# Regulator.net
KiCad netlist of a schematic drawn in Altium Designer
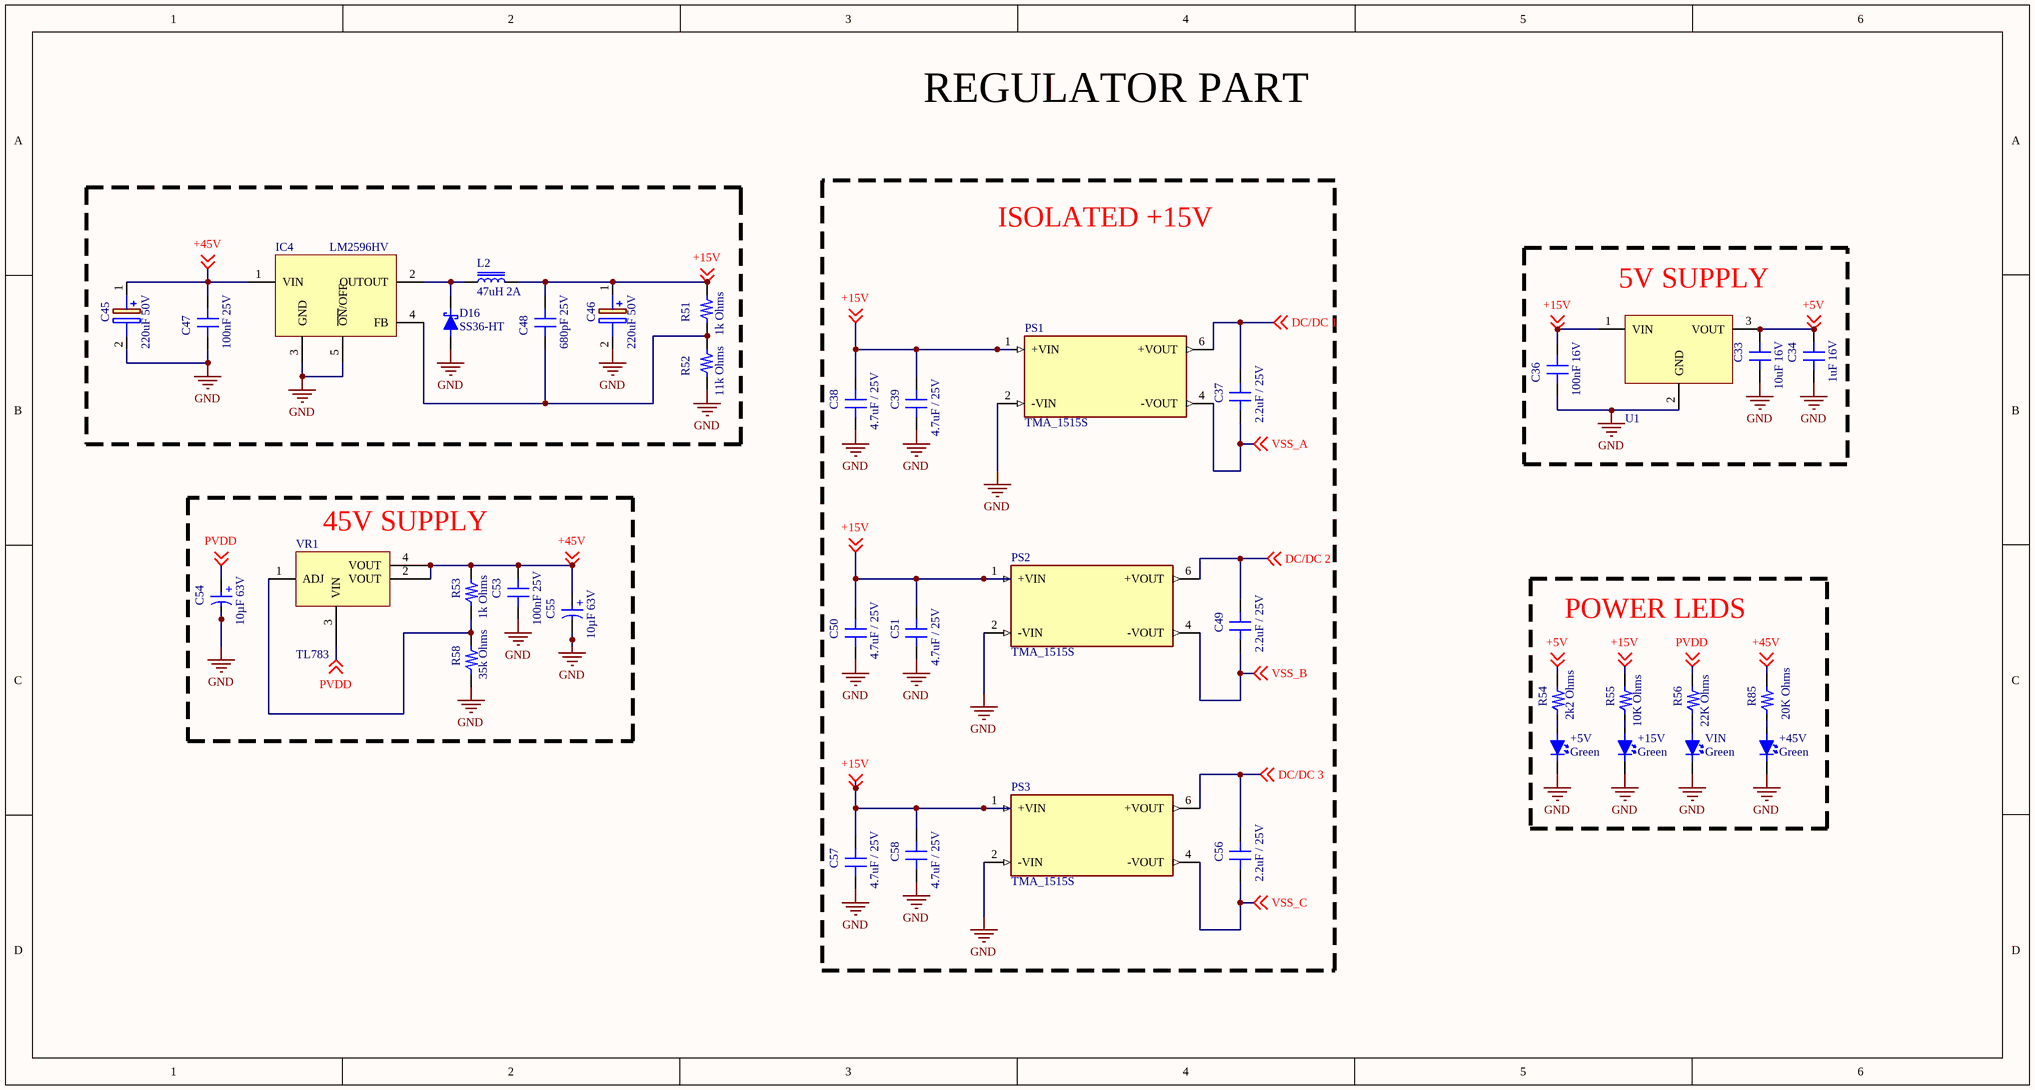
[diagram p0: Regulator.SchDoc]

(export (version "E")
  (design (tool "Eeschema 10.0.6"))
  (components
    (comp (ref "+5V")
      (value "Green")
      (footprint "0805LED")
      (description "0805")
      (libsource (lib "HidroanaSCHLib") (part "LED"))
    )
    (comp (ref "+15V")
      (value "Green")
      (footprint "0805LED")
      (description "0805")
      (libsource (lib "HidroanaSCHLib") (part "LED"))
    )
    (comp (ref "+45V")
      (value "Green")
      (footprint "0805LED")
      (description "0805")
      (libsource (lib "HidroanaSCHLib") (part "LED"))
    )
    (comp (ref "C33")
      (value "10uF 16V")
      (footprint "0805_CAP")
      (libsource (lib "HidroanaSCHLib") (part "CAP_0805"))
    )
    (comp (ref "C34")
      (value "1uF 16V")
      (footprint "0805_CAP")
      (libsource (lib "HidroanaSCHLib") (part "CAP_0805"))
    )
    (comp (ref "C36")
      (value "100nF 16V")
      (footprint "0805_CAP")
      (libsource (lib "HidroanaSCHLib") (part "CAP_0805"))
    )
    (comp (ref "C37")
      (value "2.2uF / 25V")
      (footprint "0805_CAP")
      (libsource (lib "HidroanaSCHLib") (part "CAP_0805"))
    )
    (comp (ref "C38")
      (value "4.7uF / 25V")
      (footprint "0805_CAP")
      (libsource (lib "HidroanaSCHLib") (part "CAP_0805"))
    )
    (comp (ref "C39")
      (value "4.7uF / 25V")
      (footprint "0805_CAP")
      (libsource (lib "HidroanaSCHLib") (part "CAP_0805"))
    )
    (comp (ref "C45")
      (value "220uF 50V")
      (footprint "CAPAE1030X1060N")
      (description "Capacitor Polarised")
      (fields (field (name "MANUFACTURER_PART_NUMBER") "CK1H221M-CRG10"))
      (libsource (lib "HidroanaSCHLib") (part "CK1H221M-CRG10"))
    )
    (comp (ref "C46")
      (value "220uF 50V")
      (footprint "CAPAE1030X1060N")
      (description "Capacitor Polarised")
      (fields (field (name "MANUFACTURER_PART_NUMBER") "CK1H221M-CRG10"))
      (libsource (lib "HidroanaSCHLib") (part "CK1H221M-CRG10"))
    )
    (comp (ref "C47")
      (value "100nF 25V")
      (footprint "0805_CAP")
      (libsource (lib "HidroanaSCHLib") (part "CAP_0805"))
    )
    (comp (ref "C48")
      (value "680pF 25V")
      (footprint "0805_CAP")
      (libsource (lib "HidroanaSCHLib") (part "CAP_0805"))
    )
    (comp (ref "C49")
      (value "2.2uF / 25V")
      (footprint "0805_CAP")
      (libsource (lib "HidroanaSCHLib") (part "CAP_0805"))
    )
    (comp (ref "C50")
      (value "4.7uF / 25V")
      (footprint "0805_CAP")
      (libsource (lib "HidroanaSCHLib") (part "CAP_0805"))
    )
    (comp (ref "C51")
      (value "4.7uF / 25V")
      (footprint "0805_CAP")
      (libsource (lib "HidroanaSCHLib") (part "CAP_0805"))
    )
    (comp (ref "C53")
      (value "100nF 25V")
      (footprint "0805_CAP")
      (libsource (lib "HidroanaSCHLib") (part "CAP_0805"))
    )
    (comp (ref "C54")
      (value "10µF 63V")
      (footprint "WCAP-ATG5_D5H11")
      (description "WCAP-ATG5 Aluminum Electrolytic Capacitor, Radial, THT, D5 x H11mm, 10µF, 63V")
      (fields
        (field (name "MANUFACTURER PART NUMBER") "860020772010")
        (field (name "MANUFACTURER") "Wurth Elektronik")
      )
      (libsource (lib "Hidroana Lib") (part "860020772010"))
    )
    (comp (ref "C55")
      (value "10µF 63V")
      (footprint "WCAP-ATG5_D5H11")
      (description "WCAP-ATG5 Aluminum Electrolytic Capacitor, Radial, THT, D5 x H11mm, 10µF, 63V")
      (fields
        (field (name "MANUFACTURER PART NUMBER") "860020772010")
        (field (name "MANUFACTURER") "Wurth Elektronik")
      )
      (libsource (lib "Hidroana Lib") (part "860020772010"))
    )
    (comp (ref "C56")
      (value "2.2uF / 25V")
      (footprint "0805_CAP")
      (libsource (lib "HidroanaSCHLib") (part "CAP_0805"))
    )
    (comp (ref "C57")
      (value "4.7uF / 25V")
      (footprint "0805_CAP")
      (libsource (lib "HidroanaSCHLib") (part "CAP_0805"))
    )
    (comp (ref "C58")
      (value "4.7uF / 25V")
      (footprint "0805_CAP")
      (libsource (lib "HidroanaSCHLib") (part "CAP_0805"))
    )
    (comp (ref "D16")
      (value "SS36-HT")
      (footprint "DO-214AB")
      (description "Schottky Diode")
      (libsource (lib "HidroanaSCHLib") (part "SS36-214AB-HT"))
    )
    (comp (ref "IC4")
      (value "LM2596HV")
      (footprint "TO-263-5")
      (description "Integrated Circuit")
      (fields
        (field (name "MOUSER PART NUMBER") "926-LM2596S-12")
        (field (name "ARROW PART NUMBER") "LM2596S-12")
      )
      (libsource (lib "HidroanaSCHLib") (part "LM2596HV"))
    )
    (comp (ref "L2")
      (value "47uH 2A")
      (footprint "BOURNS SRR1280")
      (description "FIXED IND 47UH 2.9A 80 MOHM SMD")
      (libsource (lib "HidroanaSCHLib") (part "Inductor"))
    )
    (comp (ref "PS1")
      (value "TMA_1515S")
      (footprint "CONV_TMA_1515S")
      (fields (field (name "MF") "{'manufacturer': u'Traco Power'}"))
      (libsource (lib "TMA_1515S") (part "TMA_1515S"))
    )
    (comp (ref "PS2")
      (value "TMA_1515S")
      (footprint "CONV_TMA_1515S")
      (fields (field (name "MF") "{'manufacturer': u'Traco Power'}"))
      (libsource (lib "TMA_1515S") (part "TMA_1515S"))
    )
    (comp (ref "PS3")
      (value "TMA_1515S")
      (footprint "CONV_TMA_1515S")
      (fields (field (name "MF") "{'manufacturer': u'Traco Power'}"))
      (libsource (lib "TMA_1515S") (part "TMA_1515S"))
    )
    (comp (ref "R51")
      (value "1k Ohms")
      (footprint "0805_RES")
      (description "0805")
      (fields (field (name "POWER") "1/8 W"))
      (libsource (lib "HidroanaSCHLib") (part "RES_0805"))
    )
    (comp (ref "R52")
      (value "11k Ohms")
      (footprint "0805_RES")
      (description "0805")
      (fields (field (name "POWER") "1/8 W"))
      (libsource (lib "HidroanaSCHLib") (part "RES_0805"))
    )
    (comp (ref "R53")
      (value "1k Ohms")
      (footprint "0805_RES")
      (description "0805")
      (fields (field (name "POWER") "1/8 W"))
      (libsource (lib "Hidroana Lib") (part "RES_0805"))
    )
    (comp (ref "R54")
      (value "2k2 Ohms")
      (footprint "0805_RES")
      (description "0805")
      (fields (field (name "POWER") "1/8 W"))
      (libsource (lib "HidroanaSCHLib") (part "RES_0805"))
    )
    (comp (ref "R55")
      (value "10K Ohms")
      (footprint "0805_RES")
      (description "0805")
      (fields (field (name "POWER") "1/8 W"))
      (libsource (lib "HidroanaSCHLib") (part "RES_0805"))
    )
    (comp (ref "R56")
      (value "22K Ohms")
      (footprint "0805_RES")
      (description "0805")
      (fields (field (name "POWER") "1/8 W"))
      (libsource (lib "HidroanaSCHLib") (part "RES_0805"))
    )
    (comp (ref "R58")
      (value "35k Ohms")
      (footprint "0805_RES")
      (description "0805")
      (fields (field (name "POWER") "1/8 W"))
      (libsource (lib "Hidroana Lib") (part "RES_0805"))
    )
    (comp (ref "R85")
      (value "20K Ohms")
      (footprint "0805_RES")
      (description "0805")
      (fields (field (name "POWER") "1/8 W"))
      (libsource (lib "HidroanaSCHLib") (part "RES_0805"))
    )
    (comp (ref "U1")
      (value "8-28Vin, 5Vout, 1Aout")
      (footprint "WPME-FDSM_SIP-3_L11.6W8.5H10.5")
      (description "WPME-FDSM Fixed Step Down Regulator Module, THT, SIP-3, 8-28Vin, 5Vout, 1Aout")
      (fields
        (field (name "MANUFACTURER PART NUMBER") "173010578")
        (field (name "MANUFACTURER") "Wurth Elektronik")
      )
      (libsource (lib "MagIC-FDSM (rev22e)") (part "173010578"))
    )
    (comp (ref "VIN")
      (value "Green")
      (footprint "0805LED")
      (description "0805")
      (libsource (lib "HidroanaSCHLib") (part "LED"))
    )
    (comp (ref "VR1")
      (value "TL783")
      (footprint "TL783")
      (libsource (lib "HidroanaSCHLib1") (part "TL783/SMD"))
    )
  )
  (nets
    (net (code "1") (name "+5V") (class "Default")
      (node (ref "C33") (pin "2") (pinfunction "2_2") (pintype "passive"))
      (node (ref "C34") (pin "2") (pinfunction "2_2") (pintype "passive"))
      (node (ref "R54") (pin "1") (pintype "passive"))
      (node (ref "U1") (pin "3") (pinfunction "VOUT_3") (pintype "passive"))
    )
    (net (code "2") (name "+15V") (class "Default")
      (node (ref "C36") (pin "2") (pinfunction "2_2") (pintype "passive"))
      (node (ref "C38") (pin "2") (pinfunction "2_2") (pintype "passive"))
      (node (ref "C39") (pin "2") (pinfunction "2_2") (pintype "passive"))
      (node (ref "C46") (pin "1") (pinfunction "+_1") (pintype "passive"))
      (node (ref "C48") (pin "2") (pinfunction "2_2") (pintype "passive"))
      (node (ref "C50") (pin "2") (pinfunction "2_2") (pintype "passive"))
      (node (ref "C51") (pin "2") (pinfunction "2_2") (pintype "passive"))
      (node (ref "C57") (pin "2") (pinfunction "2_2") (pintype "passive"))
      (node (ref "C58") (pin "2") (pinfunction "2_2") (pintype "passive"))
      (node (ref "L2") (pin "2") (pinfunction "2_2") (pintype "passive"))
      (node (ref "PS1") (pin "1") (pinfunction "+VIN_1") (pintype "input"))
      (node (ref "PS2") (pin "1") (pinfunction "+VIN_1") (pintype "input"))
      (node (ref "PS3") (pin "1") (pinfunction "+VIN_1") (pintype "input"))
      (node (ref "R51") (pin "2") (pintype "passive"))
      (node (ref "R55") (pin "1") (pintype "passive"))
      (node (ref "U1") (pin "1") (pinfunction "VIN_1") (pintype "passive"))
    )
    (net (code "3") (name "+45V") (class "Default")
      (node (ref "C45") (pin "1") (pinfunction "+_1") (pintype "passive"))
      (node (ref "C47") (pin "2") (pinfunction "2_2") (pintype "passive"))
      (node (ref "C53") (pin "2") (pinfunction "2_2") (pintype "passive"))
      (node (ref "C55") (pin "1") (pinfunction "P_1") (pintype "passive"))
      (node (ref "IC4") (pin "1") (pinfunction "VIN_1") (pintype "passive"))
      (node (ref "R53") (pin "1") (pintype "passive"))
      (node (ref "R85") (pin "1") (pintype "passive"))
      (node (ref "VR1") (pin "2") (pinfunction "VOUT_2") (pintype "passive"))
      (node (ref "VR1") (pin "4") (pinfunction "VOUT_4") (pintype "passive"))
    )
    (net (code "4") (name "DC{slash}DC 1") (class "Default")
      (node (ref "C37") (pin "2") (pinfunction "2_2") (pintype "passive"))
      (node (ref "PS1") (pin "6") (pinfunction "+VOUT_6") (pintype "output"))
    )
    (net (code "5") (name "DC{slash}DC 2") (class "Default")
      (node (ref "C49") (pin "2") (pinfunction "2_2") (pintype "passive"))
      (node (ref "PS2") (pin "6") (pinfunction "+VOUT_6") (pintype "output"))
    )
    (net (code "6") (name "DC{slash}DC 3") (class "Default")
      (node (ref "C56") (pin "2") (pinfunction "2_2") (pintype "passive"))
      (node (ref "PS3") (pin "6") (pinfunction "+VOUT_6") (pintype "output"))
    )
    (net (code "7") (name "GND") (class "Default")
      (node (ref "+15V") (pin "2") (pinfunction "Cathode(-)_2") (pintype "passive"))
      (node (ref "+45V") (pin "2") (pinfunction "Cathode(-)_2") (pintype "passive"))
      (node (ref "+5V") (pin "2") (pinfunction "Cathode(-)_2") (pintype "passive"))
      (node (ref "C33") (pin "1") (pinfunction "1_1") (pintype "passive"))
      (node (ref "C34") (pin "1") (pinfunction "1_1") (pintype "passive"))
      (node (ref "C36") (pin "1") (pinfunction "1_1") (pintype "passive"))
      (node (ref "C38") (pin "1") (pinfunction "1_1") (pintype "passive"))
      (node (ref "C39") (pin "1") (pinfunction "1_1") (pintype "passive"))
      (node (ref "C45") (pin "2") (pinfunction "-_2") (pintype "passive"))
      (node (ref "C46") (pin "2") (pinfunction "-_2") (pintype "passive"))
      (node (ref "C47") (pin "1") (pinfunction "1_1") (pintype "passive"))
      (node (ref "C50") (pin "1") (pinfunction "1_1") (pintype "passive"))
      (node (ref "C51") (pin "1") (pinfunction "1_1") (pintype "passive"))
      (node (ref "C53") (pin "1") (pinfunction "1_1") (pintype "passive"))
      (node (ref "C54") (pin "2") (pinfunction "N_2") (pintype "passive"))
      (node (ref "C55") (pin "2") (pinfunction "N_2") (pintype "passive"))
      (node (ref "C57") (pin "1") (pinfunction "1_1") (pintype "passive"))
      (node (ref "C58") (pin "1") (pinfunction "1_1") (pintype "passive"))
      (node (ref "D16") (pin "1") (pinfunction "1_1") (pintype "passive"))
      (node (ref "IC4") (pin "3") (pinfunction "GND_3") (pintype "passive"))
      (node (ref "IC4") (pin "5") (pinfunction "~{ON}/OFF_5") (pintype "passive"))
      (node (ref "PS1") (pin "2") (pinfunction "-VIN_2") (pintype "input"))
      (node (ref "PS2") (pin "2") (pinfunction "-VIN_2") (pintype "input"))
      (node (ref "PS3") (pin "2") (pinfunction "-VIN_2") (pintype "input"))
      (node (ref "R52") (pin "1") (pintype "passive"))
      (node (ref "R58") (pin "2") (pintype "passive"))
      (node (ref "U1") (pin "2") (pinfunction "GND_2") (pintype "passive"))
      (node (ref "VIN") (pin "2") (pinfunction "Cathode(-)_2") (pintype "passive"))
    )
    (net (code "8") (name "Net-(+5V-Anode(+))") (class "Default")
      (node (ref "+5V") (pin "1") (pinfunction "Anode(+)_1") (pintype "passive"))
      (node (ref "R54") (pin "2") (pintype "passive"))
    )
    (net (code "9") (name "Net-(+15V-Anode(+))") (class "Default")
      (node (ref "+15V") (pin "1") (pinfunction "Anode(+)_1") (pintype "passive"))
      (node (ref "R55") (pin "2") (pintype "passive"))
    )
    (net (code "10") (name "Net-(+45V-Anode(+))") (class "Default")
      (node (ref "+45V") (pin "1") (pinfunction "Anode(+)_1") (pintype "passive"))
      (node (ref "R85") (pin "2") (pintype "passive"))
    )
    (net (code "11") (name "Net-(IC4-FB)") (class "Default")
      (node (ref "C48") (pin "1") (pinfunction "1_1") (pintype "passive"))
      (node (ref "IC4") (pin "4") (pinfunction "FB_4") (pintype "passive"))
      (node (ref "R51") (pin "1") (pintype "passive"))
      (node (ref "R52") (pin "2") (pintype "passive"))
    )
    (net (code "12") (name "Net-(IC4-OUTOUT)") (class "Default")
      (node (ref "D16") (pin "2") (pinfunction "2_2") (pintype "passive"))
      (node (ref "IC4") (pin "2") (pinfunction "OUTOUT_2") (pintype "passive"))
      (node (ref "L2") (pin "1") (pinfunction "1_1") (pintype "passive"))
    )
    (net (code "13") (name "Net-(VIN-Anode(+))") (class "Default")
      (node (ref "R56") (pin "2") (pintype "passive"))
      (node (ref "VIN") (pin "1") (pinfunction "Anode(+)_1") (pintype "passive"))
    )
    (net (code "14") (name "Net-(VR1-ADJ)") (class "Default")
      (node (ref "R53") (pin "2") (pintype "passive"))
      (node (ref "R58") (pin "1") (pintype "passive"))
      (node (ref "VR1") (pin "1") (pinfunction "ADJ_1") (pintype "passive"))
    )
    (net (code "15") (name "PVDD") (class "Default")
      (node (ref "C54") (pin "1") (pinfunction "P_1") (pintype "passive"))
      (node (ref "R56") (pin "1") (pintype "passive"))
      (node (ref "VR1") (pin "3") (pinfunction "VIN_3") (pintype "passive"))
    )
    (net (code "16") (name "VSS_A") (class "Default")
      (node (ref "C37") (pin "1") (pinfunction "1_1") (pintype "passive"))
      (node (ref "PS1") (pin "4") (pinfunction "-VOUT_4") (pintype "output"))
    )
    (net (code "17") (name "VSS_B") (class "Default")
      (node (ref "C49") (pin "1") (pinfunction "1_1") (pintype "passive"))
      (node (ref "PS2") (pin "4") (pinfunction "-VOUT_4") (pintype "output"))
    )
    (net (code "18") (name "VSS_C") (class "Default")
      (node (ref "C56") (pin "1") (pinfunction "1_1") (pintype "passive"))
      (node (ref "PS3") (pin "4") (pinfunction "-VOUT_4") (pintype "output"))
    )
  )
)
